# Relay_board_shield.net
KiCad netlist of a schematic drawn in EAGLE
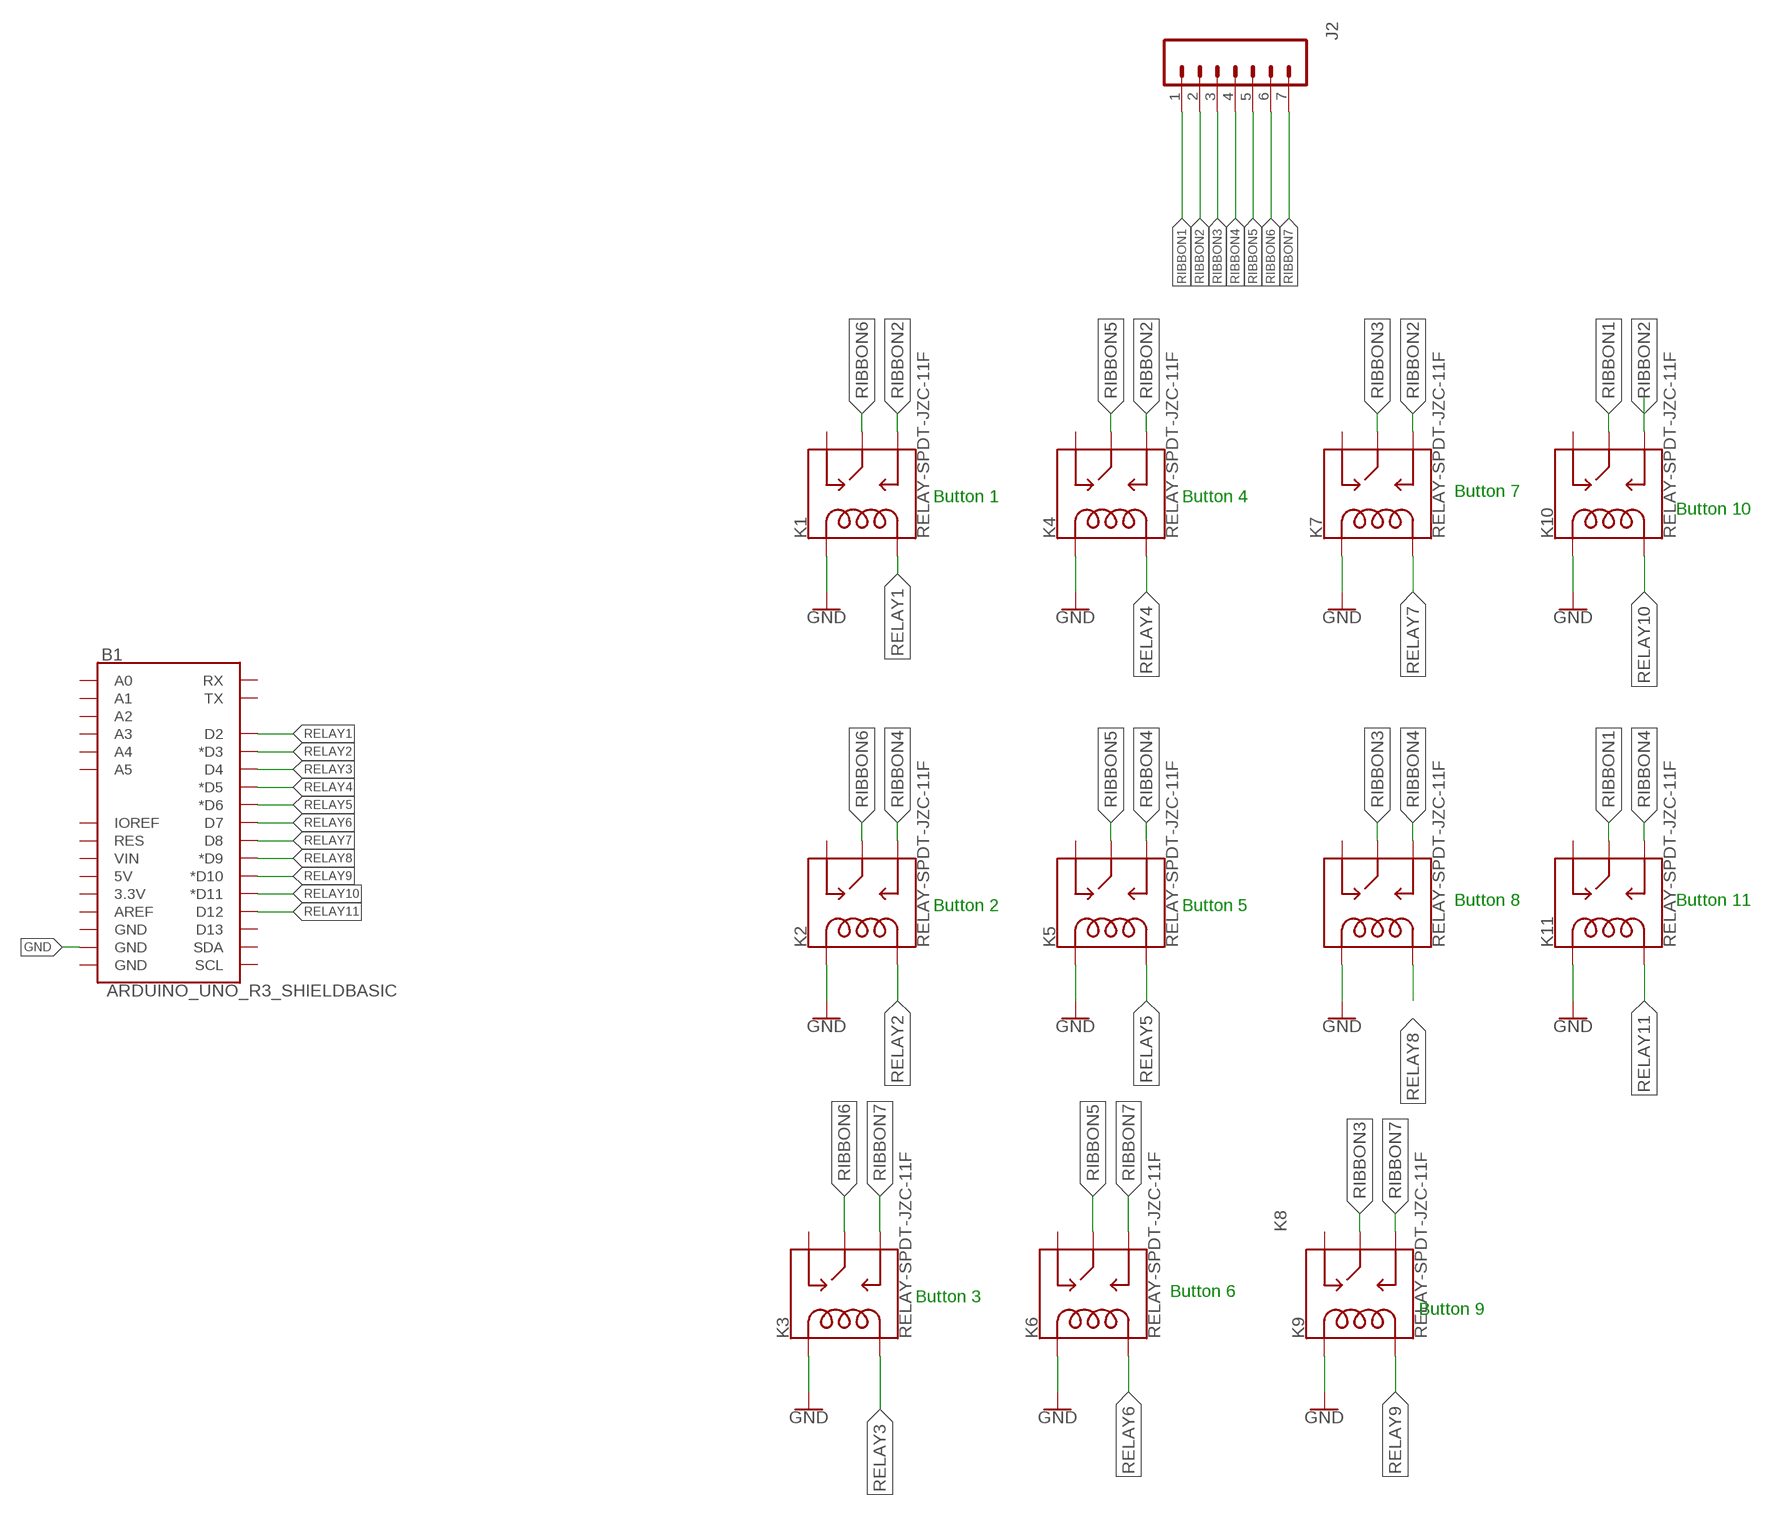
[diagram p0: schematic, sheet 1]

(export (version "E")
  (design (tool "Eeschema 10.0.6"))
  (components
    (comp (ref "B1")
      (value "ARDUINO_UNO_R3_SHIELDBASIC")
      (footprint "eagle-import:UNO_R3_SHIELD")
      (libsource (lib "eagle-import") (part "ARDUINO_UNO_R3_SHIELDBASIC"))
    )
    (comp (ref "J2")
      (value "CONN_07")
      (footprint "eagle-import:1X07")
      (libsource (lib "eagle-import") (part "CONN_07"))
    )
    (comp (ref "K1")
      (value "RELAY-SPDT-JZC-11F")
      (footprint "eagle-import:RELAY-JZC")
      (libsource (lib "eagle-import") (part "RELAY-SPDT-JZC-11F"))
    )
    (comp (ref "K2")
      (value "RELAY-SPDT-JZC-11F")
      (footprint "eagle-import:RELAY-JZC")
      (libsource (lib "eagle-import") (part "RELAY-SPDT-JZC-11F"))
    )
    (comp (ref "K3")
      (value "RELAY-SPDT-JZC-11F")
      (footprint "eagle-import:RELAY-JZC")
      (libsource (lib "eagle-import") (part "RELAY-SPDT-JZC-11F"))
    )
    (comp (ref "K4")
      (value "RELAY-SPDT-JZC-11F")
      (footprint "eagle-import:RELAY-JZC")
      (libsource (lib "eagle-import") (part "RELAY-SPDT-JZC-11F"))
    )
    (comp (ref "K5")
      (value "RELAY-SPDT-JZC-11F")
      (footprint "eagle-import:RELAY-JZC")
      (libsource (lib "eagle-import") (part "RELAY-SPDT-JZC-11F"))
    )
    (comp (ref "K6")
      (value "RELAY-SPDT-JZC-11F")
      (footprint "eagle-import:RELAY-JZC")
      (libsource (lib "eagle-import") (part "RELAY-SPDT-JZC-11F"))
    )
    (comp (ref "K7")
      (value "RELAY-SPDT-JZC-11F")
      (footprint "eagle-import:RELAY-JZC")
      (libsource (lib "eagle-import") (part "RELAY-SPDT-JZC-11F"))
    )
    (comp (ref "K8")
      (value "RELAY-SPDT-JZC-11F")
      (footprint "eagle-import:RELAY-JZC")
      (libsource (lib "eagle-import") (part "RELAY-SPDT-JZC-11F"))
    )
    (comp (ref "K9")
      (value "RELAY-SPDT-JZC-11F")
      (footprint "eagle-import:RELAY-JZC")
      (libsource (lib "eagle-import") (part "RELAY-SPDT-JZC-11F"))
    )
    (comp (ref "K10")
      (value "RELAY-SPDT-JZC-11F")
      (footprint "eagle-import:RELAY-JZC")
      (libsource (lib "eagle-import") (part "RELAY-SPDT-JZC-11F"))
    )
    (comp (ref "K11")
      (value "RELAY-SPDT-JZC-11F")
      (footprint "eagle-import:RELAY-JZC")
      (libsource (lib "eagle-import") (part "RELAY-SPDT-JZC-11F"))
    )
  )
  (nets
    (net (code "1") (name "GND") (class "Default")
      (node (ref "B1") (pin "GND@1") (pinfunction "GND_GND@1") (pintype "bidirectional"))
      (node (ref "K1") (pin "5") (pinfunction "COIL1_5") (pintype "bidirectional"))
      (node (ref "K10") (pin "5") (pinfunction "COIL1_5") (pintype "bidirectional"))
      (node (ref "K11") (pin "5") (pinfunction "COIL1_5") (pintype "bidirectional"))
      (node (ref "K2") (pin "5") (pinfunction "COIL1_5") (pintype "bidirectional"))
      (node (ref "K3") (pin "5") (pinfunction "COIL1_5") (pintype "bidirectional"))
      (node (ref "K4") (pin "5") (pinfunction "COIL1_5") (pintype "bidirectional"))
      (node (ref "K5") (pin "5") (pinfunction "COIL1_5") (pintype "bidirectional"))
      (node (ref "K6") (pin "5") (pinfunction "COIL1_5") (pintype "bidirectional"))
      (node (ref "K7") (pin "5") (pinfunction "COIL1_5") (pintype "bidirectional"))
      (node (ref "K8") (pin "5") (pinfunction "COIL1_5") (pintype "bidirectional"))
      (node (ref "K9") (pin "5") (pinfunction "COIL1_5") (pintype "bidirectional"))
    )
    (net (code "2") (name "RELAY1") (class "Default")
      (node (ref "B1") (pin "D2") (pinfunction "D2_D2") (pintype "bidirectional"))
      (node (ref "K1") (pin "1") (pinfunction "COIL2_1") (pintype "bidirectional"))
    )
    (net (code "3") (name "RELAY2") (class "Default")
      (node (ref "B1") (pin "D3") (pinfunction "*D3_D3") (pintype "bidirectional"))
      (node (ref "K2") (pin "1") (pinfunction "COIL2_1") (pintype "bidirectional"))
    )
    (net (code "4") (name "RELAY3") (class "Default")
      (node (ref "B1") (pin "D4") (pinfunction "D4_D4") (pintype "bidirectional"))
      (node (ref "K3") (pin "1") (pinfunction "COIL2_1") (pintype "bidirectional"))
    )
    (net (code "5") (name "RELAY4") (class "Default")
      (node (ref "B1") (pin "D5") (pinfunction "*D5_D5") (pintype "bidirectional"))
      (node (ref "K4") (pin "1") (pinfunction "COIL2_1") (pintype "bidirectional"))
    )
    (net (code "6") (name "RELAY5") (class "Default")
      (node (ref "B1") (pin "D6") (pinfunction "*D6_D6") (pintype "bidirectional"))
      (node (ref "K5") (pin "1") (pinfunction "COIL2_1") (pintype "bidirectional"))
    )
    (net (code "7") (name "RELAY6") (class "Default")
      (node (ref "B1") (pin "D7") (pinfunction "D7_D7") (pintype "bidirectional"))
      (node (ref "K6") (pin "1") (pinfunction "COIL2_1") (pintype "bidirectional"))
    )
    (net (code "8") (name "RELAY7") (class "Default")
      (node (ref "B1") (pin "D8") (pinfunction "D8_D8") (pintype "bidirectional"))
      (node (ref "K7") (pin "1") (pinfunction "COIL2_1") (pintype "bidirectional"))
    )
    (net (code "9") (name "RELAY8") (class "Default")
      (node (ref "B1") (pin "D9") (pinfunction "*D9_D9") (pintype "bidirectional"))
      (node (ref "K8") (pin "1") (pinfunction "COIL2_1") (pintype "bidirectional"))
    )
    (net (code "10") (name "RELAY9") (class "Default")
      (node (ref "B1") (pin "D10") (pinfunction "*D10_D10") (pintype "bidirectional"))
      (node (ref "K9") (pin "1") (pinfunction "COIL2_1") (pintype "bidirectional"))
    )
    (net (code "11") (name "RELAY10") (class "Default")
      (node (ref "B1") (pin "D11") (pinfunction "*D11_D11") (pintype "bidirectional"))
      (node (ref "K10") (pin "1") (pinfunction "COIL2_1") (pintype "bidirectional"))
    )
    (net (code "12") (name "RELAY11") (class "Default")
      (node (ref "B1") (pin "D12") (pinfunction "D12_D12") (pintype "bidirectional"))
      (node (ref "K11") (pin "1") (pinfunction "COIL2_1") (pintype "bidirectional"))
    )
    (net (code "13") (name "RIBBON1") (class "Default")
      (node (ref "J2") (pin "1") (pinfunction "1_1") (pintype "passive"))
      (node (ref "K10") (pin "4") (pinfunction "MAIN_4") (pintype "bidirectional"))
      (node (ref "K11") (pin "4") (pinfunction "MAIN_4") (pintype "bidirectional"))
    )
    (net (code "14") (name "RIBBON2") (class "Default")
      (node (ref "J2") (pin "2") (pinfunction "2_2") (pintype "passive"))
      (node (ref "K1") (pin "3") (pinfunction "NO_3") (pintype "bidirectional"))
      (node (ref "K10") (pin "3") (pinfunction "NO_3") (pintype "bidirectional"))
      (node (ref "K4") (pin "3") (pinfunction "NO_3") (pintype "bidirectional"))
      (node (ref "K7") (pin "3") (pinfunction "NO_3") (pintype "bidirectional"))
    )
    (net (code "15") (name "RIBBON3") (class "Default")
      (node (ref "J2") (pin "3") (pinfunction "3_3") (pintype "passive"))
      (node (ref "K7") (pin "4") (pinfunction "MAIN_4") (pintype "bidirectional"))
      (node (ref "K8") (pin "4") (pinfunction "MAIN_4") (pintype "bidirectional"))
      (node (ref "K9") (pin "4") (pinfunction "MAIN_4") (pintype "bidirectional"))
    )
    (net (code "16") (name "RIBBON4") (class "Default")
      (node (ref "J2") (pin "4") (pinfunction "4_4") (pintype "passive"))
      (node (ref "K11") (pin "3") (pinfunction "NO_3") (pintype "bidirectional"))
      (node (ref "K2") (pin "3") (pinfunction "NO_3") (pintype "bidirectional"))
      (node (ref "K5") (pin "3") (pinfunction "NO_3") (pintype "bidirectional"))
      (node (ref "K8") (pin "3") (pinfunction "NO_3") (pintype "bidirectional"))
    )
    (net (code "17") (name "RIBBON5") (class "Default")
      (node (ref "J2") (pin "5") (pinfunction "5_5") (pintype "passive"))
      (node (ref "K4") (pin "4") (pinfunction "MAIN_4") (pintype "bidirectional"))
      (node (ref "K5") (pin "4") (pinfunction "MAIN_4") (pintype "bidirectional"))
      (node (ref "K6") (pin "4") (pinfunction "MAIN_4") (pintype "bidirectional"))
    )
    (net (code "18") (name "RIBBON6") (class "Default")
      (node (ref "J2") (pin "6") (pinfunction "6_6") (pintype "passive"))
      (node (ref "K1") (pin "4") (pinfunction "MAIN_4") (pintype "bidirectional"))
      (node (ref "K2") (pin "4") (pinfunction "MAIN_4") (pintype "bidirectional"))
      (node (ref "K3") (pin "4") (pinfunction "MAIN_4") (pintype "bidirectional"))
    )
    (net (code "19") (name "RIBBON7") (class "Default")
      (node (ref "J2") (pin "7") (pinfunction "7_7") (pintype "passive"))
      (node (ref "K3") (pin "3") (pinfunction "NO_3") (pintype "bidirectional"))
      (node (ref "K6") (pin "3") (pinfunction "NO_3") (pintype "bidirectional"))
      (node (ref "K9") (pin "3") (pinfunction "NO_3") (pintype "bidirectional"))
    )
    (net (code "20") (name "unconnected-(B1-GND-PadGND@0)") (class "Default")
      (node (ref "B1") (pin "GND@0") (pinfunction "GND_GND@0") (pintype "bidirectional"))
    )
    (net (code "21") (name "unconnected-(B1-GND-PadGND@2)") (class "Default")
      (node (ref "B1") (pin "GND@2") (pinfunction "GND_GND@2") (pintype "bidirectional"))
    )
    (net (code "22") (name "unconnected-(B1-Pad3.3V)") (class "Default")
      (node (ref "B1") (pin "3.3V") (pinfunction "3.3V_3.3V") (pintype "bidirectional"))
    )
    (net (code "23") (name "unconnected-(B1-Pad5V)") (class "Default")
      (node (ref "B1") (pin "5V") (pinfunction "5V_5V") (pintype "bidirectional"))
    )
    (net (code "24") (name "unconnected-(B1-PadA0)") (class "Default")
      (node (ref "B1") (pin "A0") (pinfunction "A0_A0") (pintype "bidirectional"))
    )
    (net (code "25") (name "unconnected-(B1-PadA1)") (class "Default")
      (node (ref "B1") (pin "A1") (pinfunction "A1_A1") (pintype "bidirectional"))
    )
    (net (code "26") (name "unconnected-(B1-PadA2)") (class "Default")
      (node (ref "B1") (pin "A2") (pinfunction "A2_A2") (pintype "bidirectional"))
    )
    (net (code "27") (name "unconnected-(B1-PadA3)") (class "Default")
      (node (ref "B1") (pin "A3") (pinfunction "A3_A3") (pintype "bidirectional"))
    )
    (net (code "28") (name "unconnected-(B1-PadA4)") (class "Default")
      (node (ref "B1") (pin "A4") (pinfunction "A4_A4") (pintype "bidirectional"))
    )
    (net (code "29") (name "unconnected-(B1-PadA5)") (class "Default")
      (node (ref "B1") (pin "A5") (pinfunction "A5_A5") (pintype "bidirectional"))
    )
    (net (code "30") (name "unconnected-(B1-PadAREF)") (class "Default")
      (node (ref "B1") (pin "AREF") (pinfunction "AREF_AREF") (pintype "bidirectional"))
    )
    (net (code "31") (name "unconnected-(B1-PadD13)") (class "Default")
      (node (ref "B1") (pin "D13") (pinfunction "D13_D13") (pintype "bidirectional"))
    )
    (net (code "32") (name "unconnected-(B1-PadIOREF)") (class "Default")
      (node (ref "B1") (pin "IOREF") (pinfunction "IOREF_IOREF") (pintype "bidirectional"))
    )
    (net (code "33") (name "unconnected-(B1-PadRES)") (class "Default")
      (node (ref "B1") (pin "RES") (pinfunction "RES_RES") (pintype "bidirectional"))
    )
    (net (code "34") (name "unconnected-(B1-PadRX)") (class "Default")
      (node (ref "B1") (pin "RX") (pinfunction "RX_RX") (pintype "bidirectional"))
    )
    (net (code "35") (name "unconnected-(B1-PadSCL)") (class "Default")
      (node (ref "B1") (pin "SCL") (pinfunction "SCL_SCL") (pintype "bidirectional"))
    )
    (net (code "36") (name "unconnected-(B1-PadSDA)") (class "Default")
      (node (ref "B1") (pin "SDA") (pinfunction "SDA_SDA") (pintype "bidirectional"))
    )
    (net (code "37") (name "unconnected-(B1-PadTX)") (class "Default")
      (node (ref "B1") (pin "TX") (pinfunction "TX_TX") (pintype "bidirectional"))
    )
    (net (code "38") (name "unconnected-(B1-PadVIN)") (class "Default")
      (node (ref "B1") (pin "VIN") (pinfunction "VIN_VIN") (pintype "bidirectional"))
    )
    (net (code "39") (name "unconnected-(K1-NC-Pad2)") (class "Default")
      (node (ref "K1") (pin "2") (pinfunction "NC_2") (pintype "bidirectional"))
    )
    (net (code "40") (name "unconnected-(K2-NC-Pad2)") (class "Default")
      (node (ref "K2") (pin "2") (pinfunction "NC_2") (pintype "bidirectional"))
    )
    (net (code "41") (name "unconnected-(K3-NC-Pad2)") (class "Default")
      (node (ref "K3") (pin "2") (pinfunction "NC_2") (pintype "bidirectional"))
    )
    (net (code "42") (name "unconnected-(K4-NC-Pad2)") (class "Default")
      (node (ref "K4") (pin "2") (pinfunction "NC_2") (pintype "bidirectional"))
    )
    (net (code "43") (name "unconnected-(K5-NC-Pad2)") (class "Default")
      (node (ref "K5") (pin "2") (pinfunction "NC_2") (pintype "bidirectional"))
    )
    (net (code "44") (name "unconnected-(K6-NC-Pad2)") (class "Default")
      (node (ref "K6") (pin "2") (pinfunction "NC_2") (pintype "bidirectional"))
    )
    (net (code "45") (name "unconnected-(K7-NC-Pad2)") (class "Default")
      (node (ref "K7") (pin "2") (pinfunction "NC_2") (pintype "bidirectional"))
    )
    (net (code "46") (name "unconnected-(K8-NC-Pad2)") (class "Default")
      (node (ref "K8") (pin "2") (pinfunction "NC_2") (pintype "bidirectional"))
    )
    (net (code "47") (name "unconnected-(K9-NC-Pad2)") (class "Default")
      (node (ref "K9") (pin "2") (pinfunction "NC_2") (pintype "bidirectional"))
    )
    (net (code "48") (name "unconnected-(K10-NC-Pad2)") (class "Default")
      (node (ref "K10") (pin "2") (pinfunction "NC_2") (pintype "bidirectional"))
    )
    (net (code "49") (name "unconnected-(K11-NC-Pad2)") (class "Default")
      (node (ref "K11") (pin "2") (pinfunction "NC_2") (pintype "bidirectional"))
    )
  )
)
